# TemperatureController.net
KiCad netlist of a schematic drawn in Altium Designer
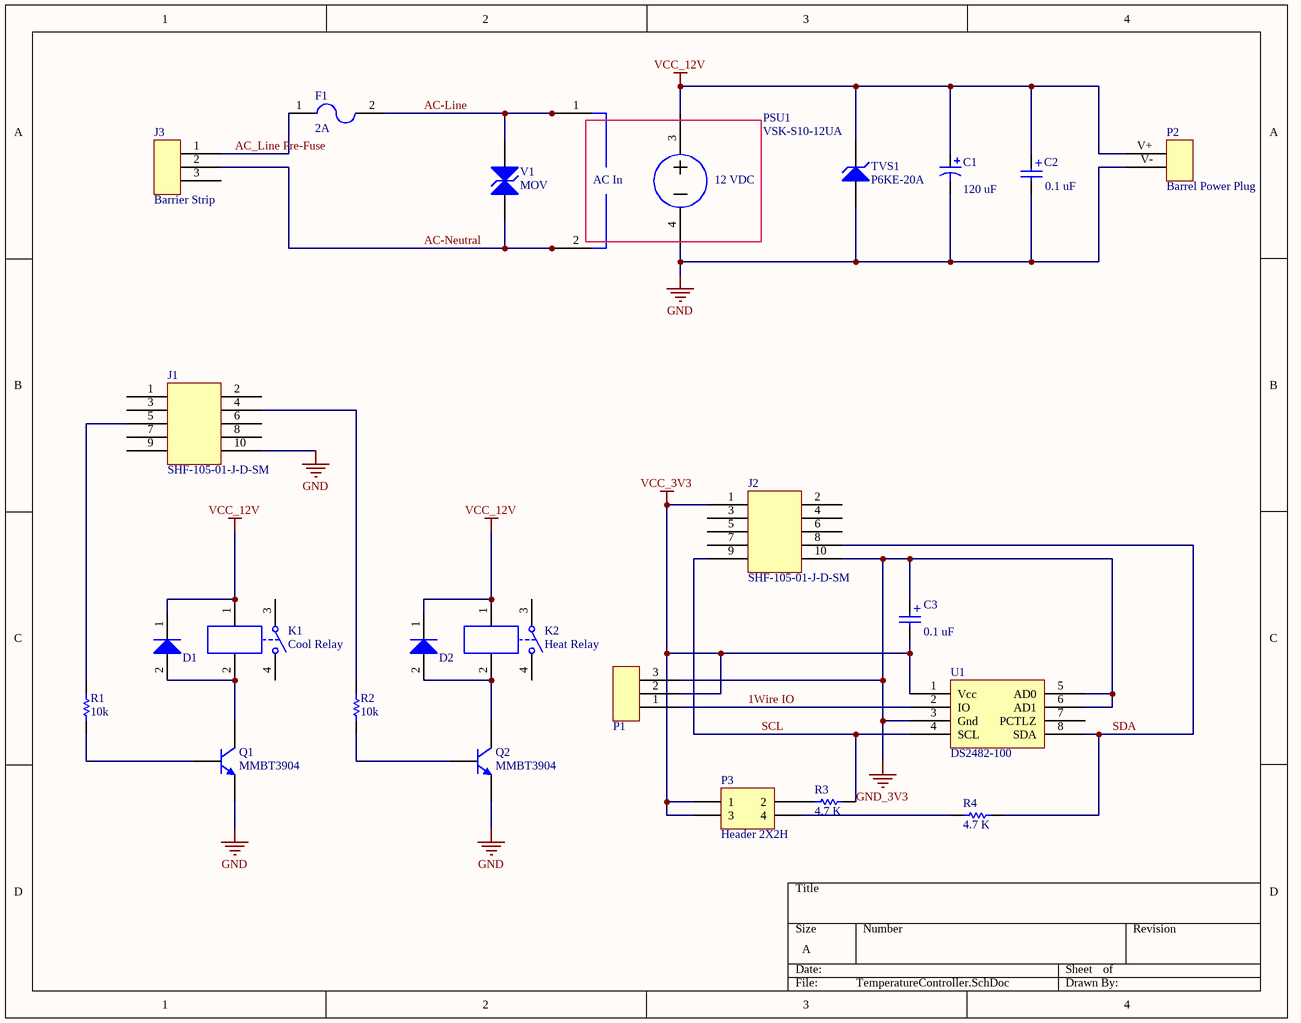
[diagram p0: TemperatureController.SchDoc]

(export (version "E")
  (design (tool "Eeschema 10.0.6"))
  (components
    (comp (ref "C1")
      (value "120 uF")
      (footprint "CAPAxial680X1220_VERT")
      (description "120 uF Aluminum Electrolytic Capacitor (Axial)")
      (fields
        (field (name "Comment") "Capacitor, Polarized Axial")
        (field (name "PUBLISHER") "Altium Limited")
      )
      (libsource (lib "James' Parts Library") (part "Capacitor, Polarized Axial"))
    )
    (comp (ref "C2")
      (value "0.1 uF")
      (footprint "0805 [2012]")
      (description "0.1 uF Capacitor SMD 0805")
      (fields (field (name "Comment") "Bypass Cap"))
      (libsource (lib "James' Parts Library") (part "Bypass Capacitor"))
    )
    (comp (ref "C3")
      (value "0.1 uF")
      (footprint "0805 [2012]")
      (description "0.1 uF Capacitor SMD 0805")
      (fields (field (name "Comment") "Bypass Cap"))
      (libsource (lib "James' Parts Library") (part "Bypass Capacitor"))
    )
    (comp (ref "D1")
      (value "SMD Diode")
      (footprint "Diode (3mm X 1mm X 4.65mm) SMD")
      (description "Diode, SMD, 0805")
      (libsource (lib "James' Parts Library") (part "Diode"))
    )
    (comp (ref "D2")
      (value "SMD Diode")
      (footprint "Diode (3mm X 1mm X 4.65mm) SMD")
      (description "Diode, SMD, 0805")
      (libsource (lib "James' Parts Library") (part "Diode"))
    )
    (comp (ref "F1")
      (value "2A")
      (footprint "Off Board Connector")
      (description "Panel Mount Fuze Holder")
      (fields (field (name "Comment") "Panel Mount Fuze"))
      (libsource (lib "James' Parts Library") (part "Panel Mount Fuse Holder"))
    )
    (comp (ref "J1")
      (value "SHF-105-01-J-D-SM")
      (footprint "Samtec SHF-105-01-J-D-SM")
      (description "Samtec 10 pin .050 pitch shrouded connector")
      (libsource (lib "James' Parts Library") (part "SHF-105-01-J-D-SM"))
    )
    (comp (ref "J2")
      (value "SHF-105-01-J-D-SM")
      (footprint "Samtec SHF-105-01-J-D-SM")
      (description "Samtec 10 pin .050 pitch shrouded connector")
      (libsource (lib "James' Parts Library") (part "SHF-105-01-J-D-SM"))
    )
    (comp (ref "J3")
      (value "Barrier Strip")
      (footprint "Molex 3 Pos Barrier Strip")
      (description "Molex 3 Pos Barrier Strip")
      (libsource (lib "James' Parts Library") (part "Molex 3 Pos Barrier Strip"))
    )
    (comp (ref "K1")
      (value "Cool Relay")
      (footprint "Omron G5CA-1A-TP")
      (description "Omron G5CA-1A-TP-E PCB Mount 12 V Relay with 15A contacts")
      (libsource (lib "James' Parts Library") (part "G5CA-1A-TP-E"))
    )
    (comp (ref "K2")
      (value "Heat Relay")
      (footprint "Omron G5CA-1A-TP")
      (description "Omron G5CA-1A-TP-E PCB Mount 12 V Relay with 15A contacts")
      (libsource (lib "James' Parts Library") (part "G5CA-1A-TP-E"))
    )
    (comp (ref "P1")
      (value "1x3 Header")
      (footprint "1x3 Pos Header")
      (description "Fan Connector Header, Single-row 3-position, 0.100\" pitch")
      (libsource (lib "James' Parts Library") (part "1x3 Header"))
    )
    (comp (ref "P2")
      (value "Barrel Power Plug")
      (footprint "Power Plug")
      (description "Power Plug")
      (libsource (lib "James' Parts Library") (part "Barrel Plug"))
    )
    (comp (ref "P3")
      (value "Header 2X2H")
      (footprint "HDR2X2H")
      (description "Header, 2-Pin, Dual row, Right Angle")
      (fields (field (name "PUBLISHER") "Altium Limited"))
      (libsource (lib "Miscellaneous Connectors") (part "Header 2X2H"))
    )
    (comp (ref "PSU1")
      (value "VSK-S10-12UA")
      (footprint "VSK-S10-12UA")
      (description "AC/DC 12V Sealed PCB Mount Power Supply")
      (libsource (lib "James' Parts Library") (part "VSK-S10-12UA"))
    )
    (comp (ref "Q1")
      (value "MMBT3904")
      (footprint "SOT-23")
      (description "NPN General Purpose Amplifier")
      (libsource (lib "James' Parts Library") (part "MMBT3904"))
    )
    (comp (ref "Q2")
      (value "MMBT3904")
      (footprint "SOT-23")
      (description "NPN General Purpose Amplifier")
      (libsource (lib "James' Parts Library") (part "MMBT3904"))
    )
    (comp (ref "R1")
      (value "10k")
      (footprint "RES_0805")
      (libsource (lib "James' Parts Library") (part "RES 0805"))
    )
    (comp (ref "R2")
      (value "10k")
      (footprint "RES_0805")
      (libsource (lib "James' Parts Library") (part "RES 0805"))
    )
    (comp (ref "R3")
      (value "4.7 K")
      (footprint "RES_0805")
      (libsource (lib "James' Parts Library") (part "RES 0805"))
    )
    (comp (ref "R4")
      (value "4.7 K")
      (footprint "RES_0805")
      (libsource (lib "James' Parts Library") (part "RES 0805"))
    )
    (comp (ref "TVS1")
      (value "P6KE-20A")
      (footprint "DIODE Axial 400 mil")
      (description "Diode, TVS, Axial")
      (libsource (lib "James' Parts Library") (part "TVS Diode"))
    )
    (comp (ref "U1")
      (value "DS2482-100")
      (footprint "DS2482-100")
      (description "I2C to 1-Wire Bridge, SO(150mil)")
      (libsource (lib "James' Parts Library") (part "DS2482"))
    )
    (comp (ref "V1")
      (value "MOV")
      (footprint "Varistor_7.62and10mm")
      (description "Metal Oxide Varistor")
      (libsource (lib "James' Parts Library") (part "MOV"))
    )
  )
  (nets
    (net (code "1") (name "/1Wire IO") (class "Default")
      (node (ref "P1") (pin "1") (pinfunction "1_1") (pintype "passive"))
      (node (ref "U1") (pin "2") (pinfunction "IO_2") (pintype "passive"))
    )
    (net (code "2") (name "/AC-Line") (class "Default")
      (node (ref "F1") (pin "2") (pinfunction "2_2") (pintype "passive"))
      (node (ref "PSU1") (pin "1") (pinfunction "1_1") (pintype "passive"))
      (node (ref "V1") (pin "2") (pinfunction "K_2") (pintype "passive"))
    )
    (net (code "3") (name "/AC-Neutral") (class "Default")
      (node (ref "J3") (pin "2") (pinfunction "2_2") (pintype "passive"))
      (node (ref "PSU1") (pin "2") (pinfunction "2_2") (pintype "passive"))
      (node (ref "V1") (pin "1") (pinfunction "A_1") (pintype "passive"))
    )
    (net (code "4") (name "/AC_Line Pre-Fuse") (class "Default")
      (node (ref "F1") (pin "1") (pinfunction "1_1") (pintype "passive"))
      (node (ref "J3") (pin "1") (pinfunction "1_1") (pintype "passive"))
    )
    (net (code "5") (name "/SCL") (class "Default")
      (node (ref "J2") (pin "9") (pinfunction "9_9") (pintype "passive"))
      (node (ref "R3") (pin "2") (pinfunction "2_2") (pintype "passive"))
      (node (ref "U1") (pin "4") (pinfunction "SCL_4") (pintype "passive"))
    )
    (net (code "6") (name "/SDA") (class "Default")
      (node (ref "J2") (pin "8") (pinfunction "8_8") (pintype "passive"))
      (node (ref "R4") (pin "1") (pinfunction "1_1") (pintype "passive"))
      (node (ref "U1") (pin "8") (pinfunction "SDA_8") (pintype "passive"))
    )
    (net (code "7") (name "GND") (class "Default")
      (node (ref "C1") (pin "2") (pinfunction "2_2") (pintype "passive"))
      (node (ref "C2") (pin "2") (pinfunction "2_2") (pintype "passive"))
      (node (ref "J1") (pin "10") (pinfunction "10_10") (pintype "passive"))
      (node (ref "P2") (pin "V-") (pinfunction "2_V-") (pintype "passive"))
      (node (ref "PSU1") (pin "4") (pinfunction "4_4") (pintype "power_in"))
      (node (ref "Q1") (pin "1") (pinfunction "E_1") (pintype "passive"))
      (node (ref "Q2") (pin "1") (pinfunction "E_1") (pintype "passive"))
      (node (ref "TVS1") (pin "1") (pinfunction "A_1") (pintype "passive"))
    )
    (net (code "8") (name "GND_3V3") (class "Default")
      (node (ref "C3") (pin "1") (pinfunction "1_1") (pintype "passive"))
      (node (ref "J2") (pin "10") (pinfunction "10_10") (pintype "passive"))
      (node (ref "P1") (pin "3") (pinfunction "3_3") (pintype "passive"))
      (node (ref "U1") (pin "3") (pinfunction "Gnd_3") (pintype "power_in"))
      (node (ref "U1") (pin "5") (pinfunction "AD0_5") (pintype "passive"))
      (node (ref "U1") (pin "6") (pinfunction "AD1_6") (pintype "passive"))
    )
    (net (code "9") (name "Net-(J1-Pad4)") (class "Default")
      (node (ref "J1") (pin "4") (pinfunction "4_4") (pintype "passive"))
      (node (ref "R2") (pin "2") (pinfunction "2_2") (pintype "passive"))
    )
    (net (code "10") (name "Net-(J1-Pad5)") (class "Default")
      (node (ref "J1") (pin "5") (pinfunction "5_5") (pintype "passive"))
      (node (ref "R1") (pin "2") (pinfunction "2_2") (pintype "passive"))
    )
    (net (code "11") (name "Net-(P3-Pad2)") (class "Default")
      (node (ref "P3") (pin "2") (pinfunction "2_2") (pintype "passive"))
      (node (ref "R3") (pin "1") (pinfunction "1_1") (pintype "passive"))
    )
    (net (code "12") (name "Net-(P3-Pad4)") (class "Default")
      (node (ref "P3") (pin "4") (pinfunction "4_4") (pintype "passive"))
      (node (ref "R4") (pin "2") (pinfunction "2_2") (pintype "passive"))
    )
    (net (code "13") (name "Net-(Q1-B)") (class "Default")
      (node (ref "Q1") (pin "2") (pinfunction "B_2") (pintype "passive"))
      (node (ref "R1") (pin "1") (pinfunction "1_1") (pintype "passive"))
    )
    (net (code "14") (name "Net-(Q1-C)") (class "Default")
      (node (ref "D1") (pin "2") (pinfunction "2_2") (pintype "passive"))
      (node (ref "K1") (pin "2") (pinfunction "2_2") (pintype "passive"))
      (node (ref "Q1") (pin "3") (pinfunction "C_3") (pintype "passive"))
    )
    (net (code "15") (name "Net-(Q2-B)") (class "Default")
      (node (ref "Q2") (pin "2") (pinfunction "B_2") (pintype "passive"))
      (node (ref "R2") (pin "1") (pinfunction "1_1") (pintype "passive"))
    )
    (net (code "16") (name "Net-(Q2-C)") (class "Default")
      (node (ref "D2") (pin "2") (pinfunction "2_2") (pintype "passive"))
      (node (ref "K2") (pin "2") (pinfunction "2_2") (pintype "passive"))
      (node (ref "Q2") (pin "3") (pinfunction "C_3") (pintype "passive"))
    )
    (net (code "17") (name "VCC_3V3") (class "Default")
      (node (ref "C3") (pin "2") (pinfunction "2_2") (pintype "passive"))
      (node (ref "J2") (pin "1") (pinfunction "1_1") (pintype "passive"))
      (node (ref "P1") (pin "2") (pinfunction "2_2") (pintype "passive"))
      (node (ref "P3") (pin "1") (pinfunction "1_1") (pintype "passive"))
      (node (ref "P3") (pin "3") (pinfunction "3_3") (pintype "passive"))
      (node (ref "U1") (pin "1") (pinfunction "Vcc_1") (pintype "power_in"))
    )
    (net (code "18") (name "VCC_12V") (class "Default")
      (node (ref "C1") (pin "1") (pinfunction "1_1") (pintype "passive"))
      (node (ref "C2") (pin "1") (pinfunction "1_1") (pintype "passive"))
      (node (ref "D1") (pin "1") (pinfunction "1_1") (pintype "passive"))
      (node (ref "D2") (pin "1") (pinfunction "1_1") (pintype "passive"))
      (node (ref "K1") (pin "1") (pinfunction "1_1") (pintype "passive"))
      (node (ref "K2") (pin "1") (pinfunction "1_1") (pintype "passive"))
      (node (ref "P2") (pin "V+") (pinfunction "V+_V+") (pintype "passive"))
      (node (ref "PSU1") (pin "3") (pinfunction "3_3") (pintype "power_in"))
      (node (ref "TVS1") (pin "2") (pinfunction "K_2") (pintype "passive"))
    )
    (net (code "19") (name "unconnected-(J1-Pad1)") (class "Default")
      (node (ref "J1") (pin "1") (pinfunction "1_1") (pintype "passive"))
    )
    (net (code "20") (name "unconnected-(J1-Pad2)") (class "Default")
      (node (ref "J1") (pin "2") (pinfunction "2_2") (pintype "passive"))
    )
    (net (code "21") (name "unconnected-(J1-Pad3)") (class "Default")
      (node (ref "J1") (pin "3") (pinfunction "3_3") (pintype "passive"))
    )
    (net (code "22") (name "unconnected-(J1-Pad6)") (class "Default")
      (node (ref "J1") (pin "6") (pinfunction "6_6") (pintype "passive"))
    )
    (net (code "23") (name "unconnected-(J1-Pad7)") (class "Default")
      (node (ref "J1") (pin "7") (pinfunction "7_7") (pintype "passive"))
    )
    (net (code "24") (name "unconnected-(J1-Pad8)") (class "Default")
      (node (ref "J1") (pin "8") (pinfunction "8_8") (pintype "passive"))
    )
    (net (code "25") (name "unconnected-(J1-Pad9)") (class "Default")
      (node (ref "J1") (pin "9") (pinfunction "9_9") (pintype "passive"))
    )
    (net (code "26") (name "unconnected-(J2-Pad2)") (class "Default")
      (node (ref "J2") (pin "2") (pinfunction "2_2") (pintype "passive"))
    )
    (net (code "27") (name "unconnected-(J2-Pad3)") (class "Default")
      (node (ref "J2") (pin "3") (pinfunction "3_3") (pintype "passive"))
    )
    (net (code "28") (name "unconnected-(J2-Pad4)") (class "Default")
      (node (ref "J2") (pin "4") (pinfunction "4_4") (pintype "passive"))
    )
    (net (code "29") (name "unconnected-(J2-Pad5)") (class "Default")
      (node (ref "J2") (pin "5") (pinfunction "5_5") (pintype "passive"))
    )
    (net (code "30") (name "unconnected-(J2-Pad6)") (class "Default")
      (node (ref "J2") (pin "6") (pinfunction "6_6") (pintype "passive"))
    )
    (net (code "31") (name "unconnected-(J2-Pad7)") (class "Default")
      (node (ref "J2") (pin "7") (pinfunction "7_7") (pintype "passive"))
    )
    (net (code "32") (name "unconnected-(J3-Pad3)") (class "Default")
      (node (ref "J3") (pin "3") (pinfunction "3_3") (pintype "passive"))
    )
    (net (code "33") (name "unconnected-(K1-Pad3)") (class "Default")
      (node (ref "K1") (pin "3") (pinfunction "3_3") (pintype "passive"))
    )
    (net (code "34") (name "unconnected-(K1-Pad4)") (class "Default")
      (node (ref "K1") (pin "4") (pinfunction "4_4") (pintype "passive"))
    )
    (net (code "35") (name "unconnected-(K2-Pad3)") (class "Default")
      (node (ref "K2") (pin "3") (pinfunction "3_3") (pintype "passive"))
    )
    (net (code "36") (name "unconnected-(K2-Pad4)") (class "Default")
      (node (ref "K2") (pin "4") (pinfunction "4_4") (pintype "passive"))
    )
    (net (code "37") (name "unconnected-(U1-PCTLZ-Pad7)") (class "Default")
      (node (ref "U1") (pin "7") (pinfunction "PCTLZ_7") (pintype "passive"))
    )
  )
)
